# CONNECTORS.net
KiCad netlist of a schematic drawn in Altium Designer
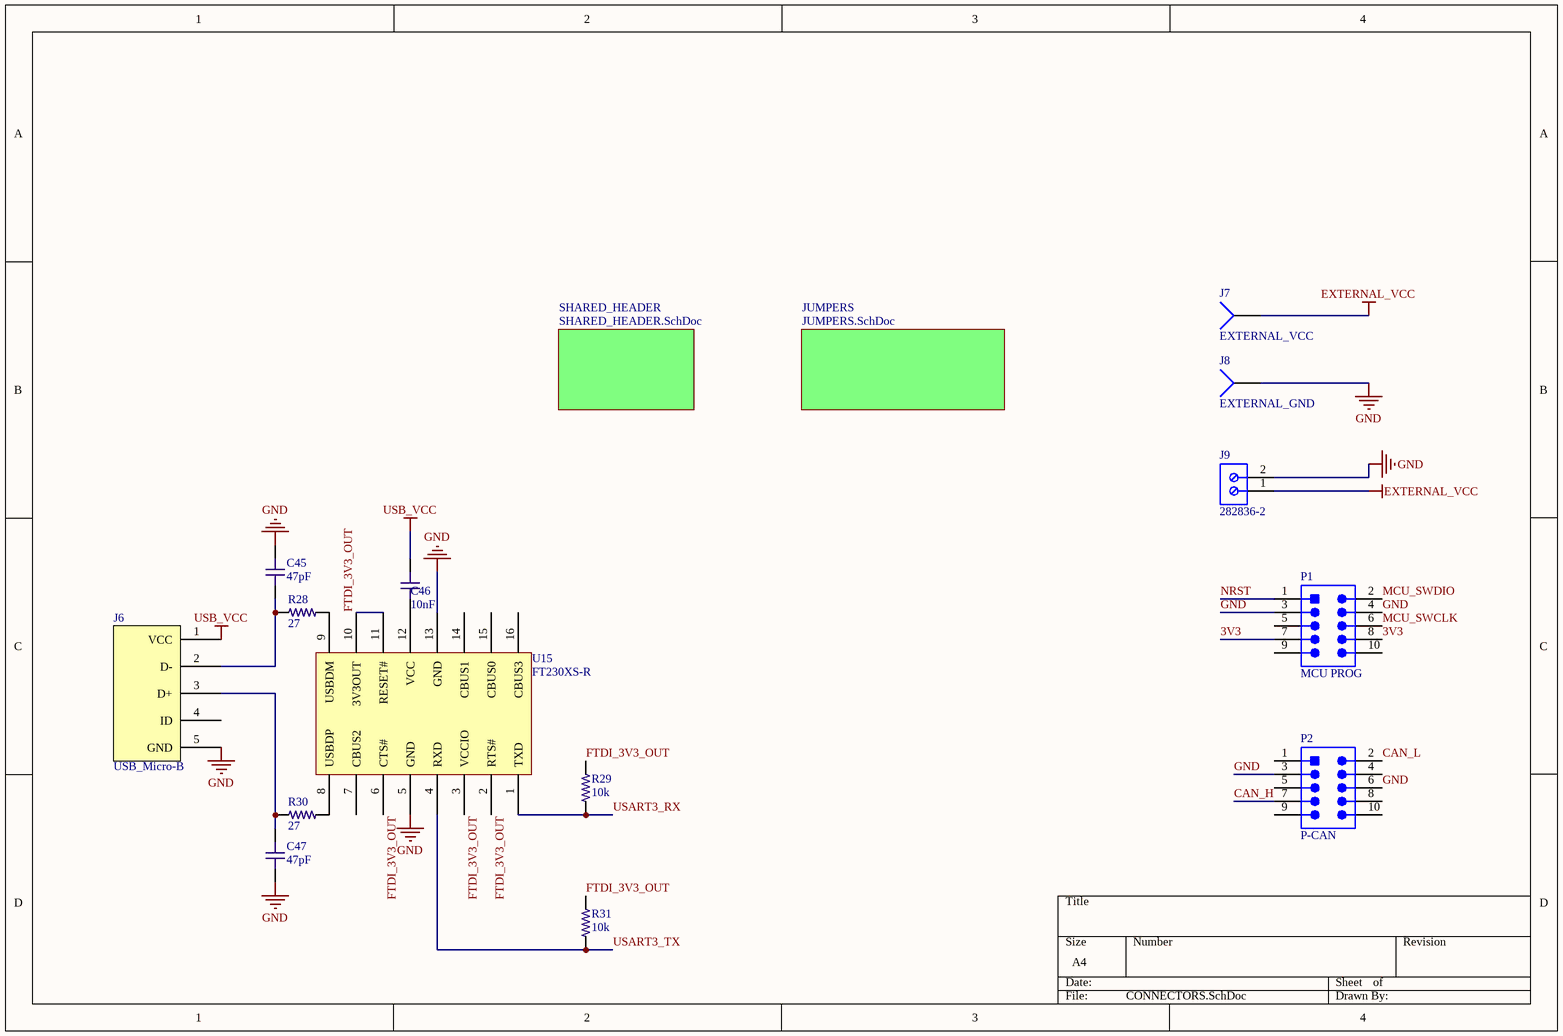
[diagram p0: CONNECTORS.SchDoc]

(export (version "E")
  (design (tool "Eeschema 10.0.6"))
  (components
    (comp (ref "C45")
      (value "47pF")
      (footprint "C0603-IPC")
      (description "Chip Capacitor, 0603, ??nF, 10V, X7R")
      (fields (field (name "Comment") "0603 Capacitor Template"))
      (libsource (lib "Capacitors") (part "0603 Capacitor Template"))
    )
    (comp (ref "C46")
      (value "10nF")
      (footprint "C0603-IPC")
      (description "Chip Capacitor, 0603, ??nF, 10V, X7R")
      (fields (field (name "Comment") "0603 Capacitor Template"))
      (libsource (lib "Capacitors") (part "0603 Capacitor Template"))
    )
    (comp (ref "C47")
      (value "47pF")
      (footprint "C0603-IPC")
      (description "Chip Capacitor, 0603, ??nF, 10V, X7R")
      (fields (field (name "Comment") "0603 Capacitor Template"))
      (libsource (lib "Capacitors") (part "0603 Capacitor Template"))
    )
    (comp (ref "J6")
      (value "USB_Micro-B")
      (footprint "USB_Micro-B")
      (description "USB Micro-B")
      (fields
        (field (name "MANUFACTURER") "Amphenol ICC (FCI)")
        (field (name "PART NUMBER") "10118193-0001LF")
      )
      (libsource (lib "UBC_Orbit_Shared_Components") (part "USB_Micro-B"))
    )
    (comp (ref "J7")
      (value "EXTERNAL_VCC")
      (footprint "Red-BananaJack")
      (description "Socket")
      (fields (field (name "PUBLISHER") "Altium Limited"))
      (libsource (lib "Miscellaneous Connectors") (part "Socket"))
    )
    (comp (ref "J8")
      (value "EXTERNAL_GND")
      (footprint "Black-BananaJack")
      (description "Socket")
      (fields (field (name "PUBLISHER") "Altium Limited"))
      (libsource (lib "Miscellaneous Connectors") (part "Socket"))
    )
    (comp (ref "J9")
      (value "282836-2")
      (footprint "TECO-282836-2_V")
      (description "Female Header, Pitch 5 mm, 1 x 2 Position, Height 10 mm, Tail Length 3.5 mm, Rohs, Bulk")
      (fields (field (name "VOLTAGE") "300V") (field (name "MANUFACTURER") "TE Connectivity"))
      (libsource (lib "Altium Content Vault") (part "CN-1P-F-TB2"))
    )
    (comp (ref "P1")
      (value "MCU PROG")
      (footprint "3M-N2510-6002-10_V")
      (fields (field (name "PARTNUMBER") "N2510") (field (name "MANUFACTURER") "3M"))
      (libsource (lib "Altium Content Vault") (part "CN-2P-M-R10"))
    )
    (comp (ref "P2")
      (value "P-CAN")
      (footprint "3M-N2510-6002-10_V")
      (fields (field (name "PARTNUMBER") "N2510") (field (name "MANUFACTURER") "3M"))
      (libsource (lib "Altium Content Vault") (part "CN-2P-M-R10"))
    )
    (comp (ref "R28")
      (value "27")
      (footprint "R0603-IPC")
      (description "Chip Resistor, 0603, ??k ohms, 0.1W")
      (fields (field (name "Comment") "0603 Template"))
      (libsource (lib "Resistors") (part "0603 Template"))
    )
    (comp (ref "R29")
      (value "10k")
      (footprint "R0603-IPC")
      (description "Chip Resistor, 0603, ??k ohms, 0.1W")
      (fields (field (name "Comment") "0603 Template"))
      (libsource (lib "Resistors") (part "0603 Template"))
    )
    (comp (ref "R30")
      (value "27")
      (footprint "R0603-IPC")
      (description "Chip Resistor, 0603, ??k ohms, 0.1W")
      (fields (field (name "Comment") "0603 Template"))
      (libsource (lib "Resistors") (part "0603 Template"))
    )
    (comp (ref "R31")
      (value "10k")
      (footprint "R0603-IPC")
      (description "Chip Resistor, 0603, ??k ohms, 0.1W")
      (fields (field (name "Comment") "0603 Template"))
      (libsource (lib "Resistors") (part "0603 Template"))
    )
    (comp (ref "U15")
      (value "FT230XS-R")
      (footprint "SOP64P600X175-16N")
      (description "FT230XS-R USB to UART IC")
      (fields (field (name "MANUFACTURER") "FTDI, Future Technology Devices International Ltd"))
      (libsource (lib "UBC_Orbit_Shared_Components") (part "FT230XS-R"))
    )
  )
  (nets
    (net (code "1") (name "/3V3") (class "Default")
      (node (ref "P1") (pin "7") (pinfunction "7_7") (pintype "passive"))
      (node (ref "P1") (pin "8") (pinfunction "8_8") (pintype "passive"))
    )
    (net (code "2") (name "/CAN_H") (class "Default")
      (node (ref "P2") (pin "7") (pinfunction "7_7") (pintype "passive"))
    )
    (net (code "3") (name "/CAN_L") (class "Default")
      (node (ref "P2") (pin "2") (pinfunction "2_2") (pintype "passive"))
    )
    (net (code "4") (name "/FTDI_3V3_OUT") (class "Default")
      (node (ref "R29") (pin "2") (pintype "passive"))
      (node (ref "R31") (pin "2") (pintype "passive"))
      (node (ref "U15") (pin "10") (pinfunction "3V3OUT_10") (pintype "passive"))
      (node (ref "U15") (pin "11") (pinfunction "RESET#_11") (pintype "passive"))
      (node (ref "U15") (pin "2") (pinfunction "RTS#_2") (pintype "passive"))
      (node (ref "U15") (pin "3") (pinfunction "VCCIO_3") (pintype "passive"))
      (node (ref "U15") (pin "6") (pinfunction "CTS#_6") (pintype "passive"))
    )
    (net (code "5") (name "/MCU_SWCLK") (class "Default")
      (node (ref "P1") (pin "6") (pinfunction "6_6") (pintype "passive"))
    )
    (net (code "6") (name "/MCU_SWDIO") (class "Default")
      (node (ref "P1") (pin "2") (pinfunction "2_2") (pintype "passive"))
    )
    (net (code "7") (name "/NRST") (class "Default")
      (node (ref "P1") (pin "1") (pinfunction "1_1") (pintype "passive"))
    )
    (net (code "8") (name "/USART3_RX") (class "Default")
      (node (ref "R29") (pin "1") (pintype "passive"))
      (node (ref "U15") (pin "1") (pinfunction "TXD_1") (pintype "passive"))
    )
    (net (code "9") (name "/USART3_TX") (class "Default")
      (node (ref "R31") (pin "1") (pintype "passive"))
      (node (ref "U15") (pin "4") (pinfunction "RXD_4") (pintype "passive"))
    )
    (net (code "10") (name "EXTERNAL_VCC") (class "Default")
      (node (ref "J7") (pin "1") (pinfunction "1_1") (pintype "passive"))
      (node (ref "J9") (pin "1") (pinfunction "1_1") (pintype "passive"))
    )
    (net (code "11") (name "GND") (class "Default")
      (node (ref "C45") (pin "2") (pintype "passive"))
      (node (ref "C47") (pin "1") (pintype "passive"))
      (node (ref "J6") (pin "5") (pinfunction "GND_5") (pintype "passive"))
      (node (ref "J8") (pin "1") (pinfunction "1_1") (pintype "passive"))
      (node (ref "J9") (pin "2") (pinfunction "2_2") (pintype "passive"))
      (node (ref "P1") (pin "3") (pinfunction "3_3") (pintype "passive"))
      (node (ref "P1") (pin "4") (pinfunction "4_4") (pintype "passive"))
      (node (ref "P2") (pin "3") (pinfunction "3_3") (pintype "passive"))
      (node (ref "P2") (pin "6") (pinfunction "6_6") (pintype "passive"))
      (node (ref "U15") (pin "13") (pinfunction "GND_13") (pintype "passive"))
      (node (ref "U15") (pin "5") (pinfunction "GND_5") (pintype "passive"))
    )
    (net (code "12") (name "Net-(J6-D+)") (class "Default")
      (node (ref "C47") (pin "2") (pintype "passive"))
      (node (ref "J6") (pin "3") (pinfunction "D+_3") (pintype "passive"))
      (node (ref "R30") (pin "1") (pintype "passive"))
    )
    (net (code "13") (name "Net-(J6-D-)") (class "Default")
      (node (ref "C45") (pin "1") (pintype "passive"))
      (node (ref "J6") (pin "2") (pinfunction "D-_2") (pintype "passive"))
      (node (ref "R28") (pin "1") (pintype "passive"))
    )
    (net (code "14") (name "Net-(U15-USBDM)") (class "Default")
      (node (ref "R28") (pin "2") (pintype "passive"))
      (node (ref "U15") (pin "9") (pinfunction "USBDM_9") (pintype "passive"))
    )
    (net (code "15") (name "Net-(U15-USBDP)") (class "Default")
      (node (ref "R30") (pin "2") (pintype "passive"))
      (node (ref "U15") (pin "8") (pinfunction "USBDP_8") (pintype "passive"))
    )
    (net (code "16") (name "Net-(U15-VCC)") (class "Default")
      (node (ref "C46") (pin "1") (pintype "passive"))
      (node (ref "U15") (pin "12") (pinfunction "VCC_12") (pintype "passive"))
    )
    (net (code "17") (name "USB_VCC") (class "Default")
      (node (ref "C46") (pin "2") (pintype "passive"))
      (node (ref "J6") (pin "1") (pinfunction "VCC_1") (pintype "passive"))
    )
    (net (code "18") (name "unconnected-(J6-ID-Pad4)") (class "Default")
      (node (ref "J6") (pin "4") (pinfunction "ID_4") (pintype "passive"))
    )
    (net (code "19") (name "unconnected-(P1-Pad5)") (class "Default")
      (node (ref "P1") (pin "5") (pinfunction "5_5") (pintype "passive"))
    )
    (net (code "20") (name "unconnected-(P1-Pad9)") (class "Default")
      (node (ref "P1") (pin "9") (pinfunction "9_9") (pintype "passive"))
    )
    (net (code "21") (name "unconnected-(P1-Pad10)") (class "Default")
      (node (ref "P1") (pin "10") (pinfunction "10_10") (pintype "passive"))
    )
    (net (code "22") (name "unconnected-(P2-Pad1)") (class "Default")
      (node (ref "P2") (pin "1") (pinfunction "1_1") (pintype "passive"))
    )
    (net (code "23") (name "unconnected-(P2-Pad4)") (class "Default")
      (node (ref "P2") (pin "4") (pinfunction "4_4") (pintype "passive"))
    )
    (net (code "24") (name "unconnected-(P2-Pad5)") (class "Default")
      (node (ref "P2") (pin "5") (pinfunction "5_5") (pintype "passive"))
    )
    (net (code "25") (name "unconnected-(P2-Pad8)") (class "Default")
      (node (ref "P2") (pin "8") (pinfunction "8_8") (pintype "passive"))
    )
    (net (code "26") (name "unconnected-(P2-Pad9)") (class "Default")
      (node (ref "P2") (pin "9") (pinfunction "9_9") (pintype "passive"))
    )
    (net (code "27") (name "unconnected-(P2-Pad10)") (class "Default")
      (node (ref "P2") (pin "10") (pinfunction "10_10") (pintype "passive"))
    )
    (net (code "28") (name "unconnected-(U15-CBUS0-Pad15)") (class "Default")
      (node (ref "U15") (pin "15") (pinfunction "CBUS0_15") (pintype "passive"))
    )
    (net (code "29") (name "unconnected-(U15-CBUS1-Pad14)") (class "Default")
      (node (ref "U15") (pin "14") (pinfunction "CBUS1_14") (pintype "passive"))
    )
    (net (code "30") (name "unconnected-(U15-CBUS2-Pad7)") (class "Default")
      (node (ref "U15") (pin "7") (pinfunction "CBUS2_7") (pintype "passive"))
    )
    (net (code "31") (name "unconnected-(U15-CBUS3-Pad16)") (class "Default")
      (node (ref "U15") (pin "16") (pinfunction "CBUS3_16") (pintype "passive"))
    )
  )
)
